# ArduinoStandaloneUsbSwitch-V2.net
KiCad netlist of a schematic drawn in EAGLE
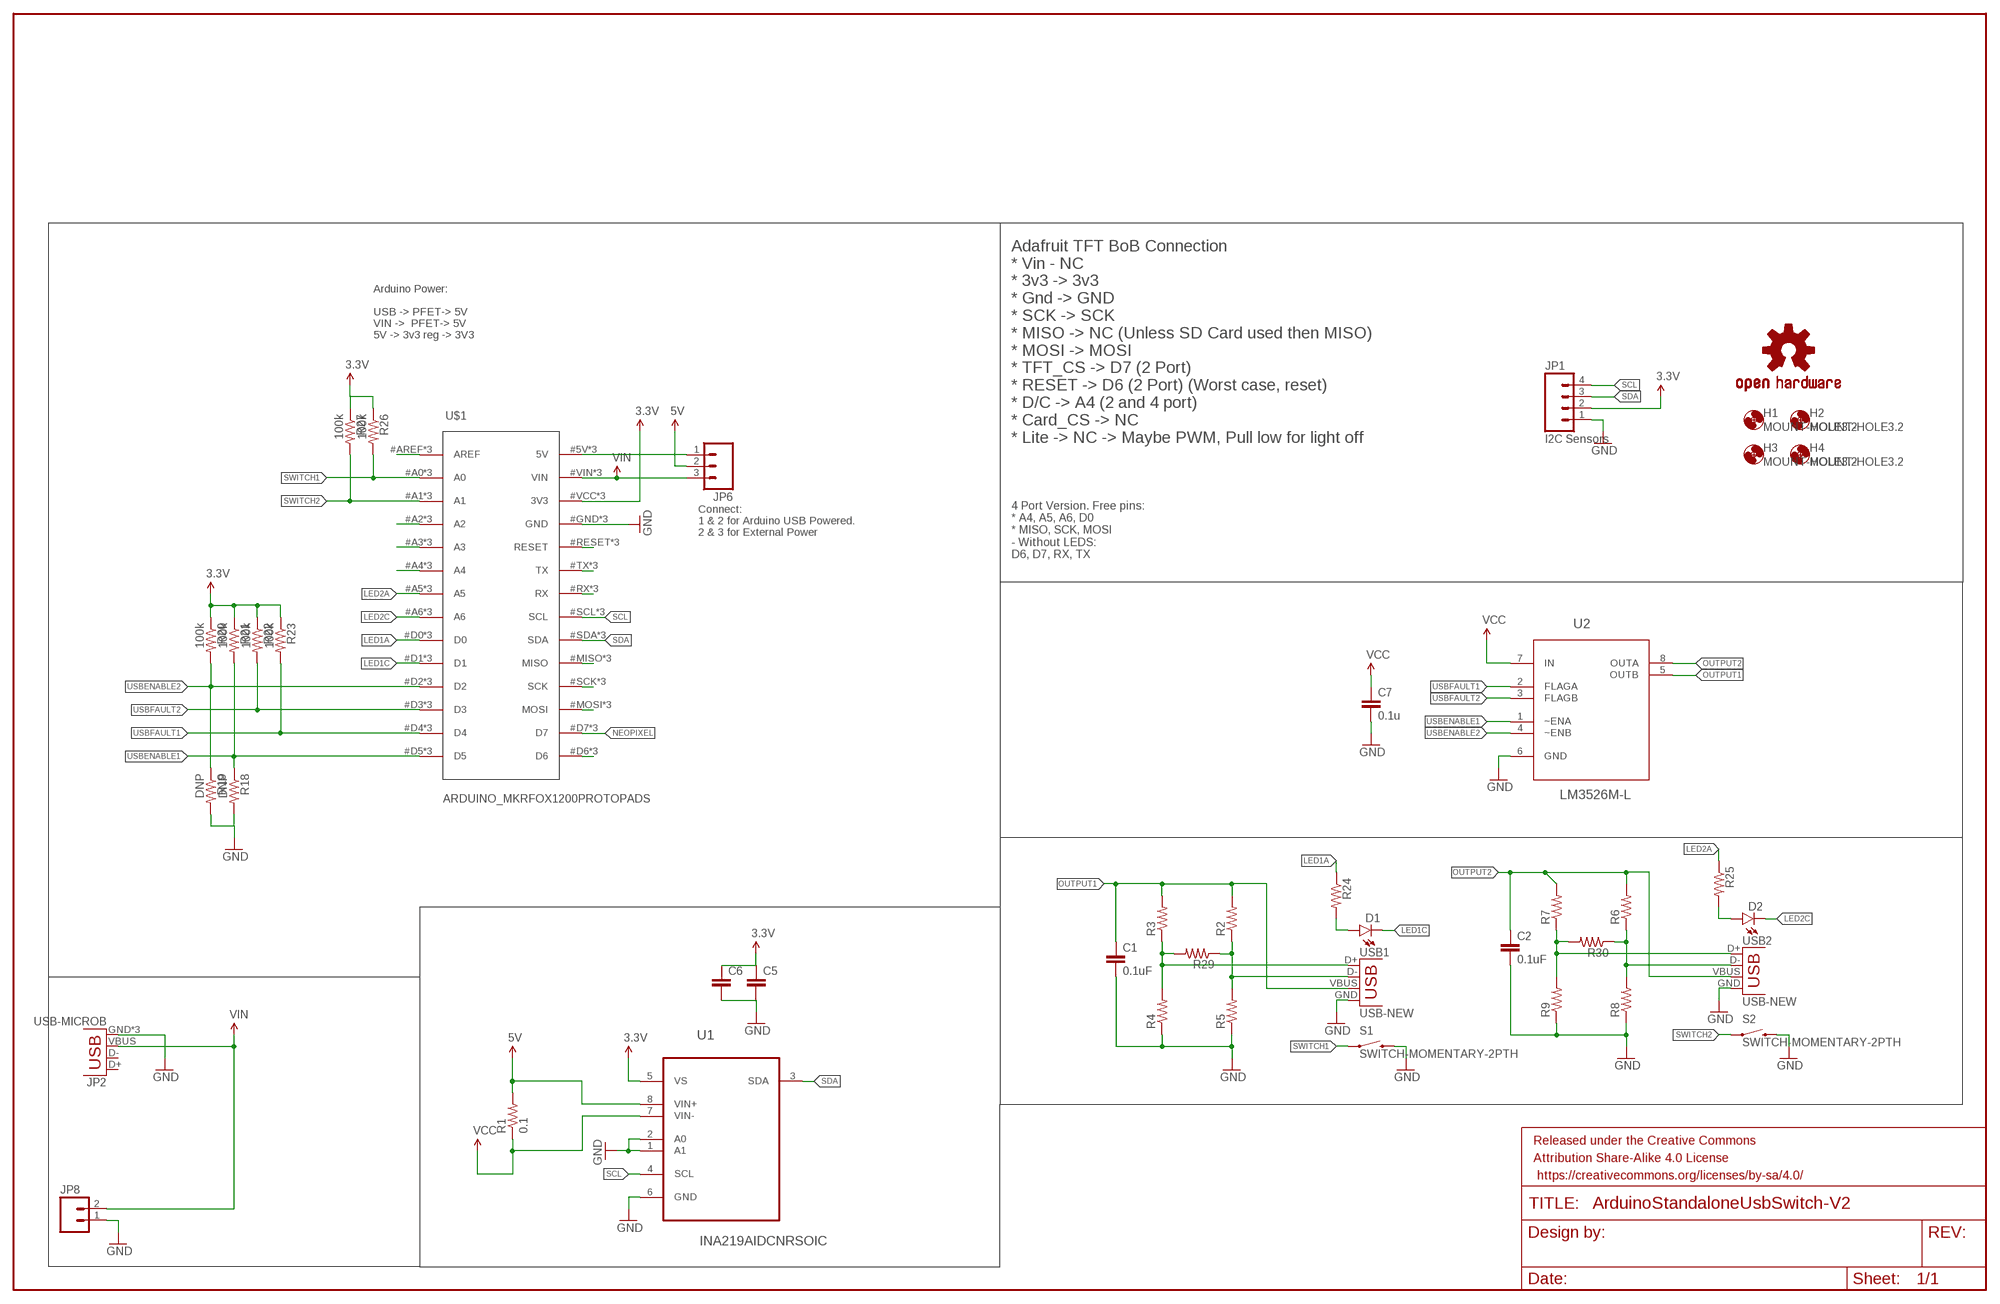
[diagram p0: schematic, sheet 1]

(export (version "E")
  (design (tool "Eeschema 10.0.6"))
  (components
    (comp (ref "C1")
      (value "0.1uF")
      (footprint "eagle-import:0805")
      (libsource (lib "eagle-import") (part "CAP0805"))
    )
    (comp (ref "C2")
      (value "0.1uF")
      (footprint "eagle-import:0805")
      (libsource (lib "eagle-import") (part "CAP0805"))
    )
    (comp (ref "C5")
      (value "CAP0805")
      (footprint "eagle-import:0805")
      (libsource (lib "eagle-import") (part "CAP0805"))
    )
    (comp (ref "C6")
      (value "CAP0805")
      (footprint "eagle-import:0805")
      (libsource (lib "eagle-import") (part "CAP0805"))
    )
    (comp (ref "C7")
      (value "0.1u")
      (footprint "eagle-import:0805")
      (libsource (lib "eagle-import") (part "CAP0805"))
    )
    (comp (ref "D1")
      (value "LED3MM")
      (footprint "eagle-import:LED3MM")
      (libsource (lib "eagle-import") (part "LED3MM"))
    )
    (comp (ref "D2")
      (value "LED3MM")
      (footprint "eagle-import:LED3MM")
      (libsource (lib "eagle-import") (part "LED3MM"))
    )
    (comp (ref "FRAME1")
      (value "FRAME-LEDGER")
      (footprint "eagle-import:CREATIVE_COMMONS")
      (libsource (lib "eagle-import") (part "FRAME-LEDGER"))
    )
    (comp (ref "H1")
      (value "MOUNT-HOLE3.2")
      (footprint "eagle-import:3,2")
      (libsource (lib "eagle-import") (part "MOUNT-HOLE3.2"))
    )
    (comp (ref "H2")
      (value "MOUNT-HOLE3.2")
      (footprint "eagle-import:3,2")
      (libsource (lib "eagle-import") (part "MOUNT-HOLE3.2"))
    )
    (comp (ref "H3")
      (value "MOUNT-HOLE3.2")
      (footprint "eagle-import:3,2")
      (libsource (lib "eagle-import") (part "MOUNT-HOLE3.2"))
    )
    (comp (ref "H4")
      (value "MOUNT-HOLE3.2")
      (footprint "eagle-import:3,2")
      (libsource (lib "eagle-import") (part "MOUNT-HOLE3.2"))
    )
    (comp (ref "JP1")
      (value "I2C Sensors")
      (footprint "eagle-import:MOLEX-1X4")
      (libsource (lib "eagle-import") (part "M04POLAR"))
    )
    (comp (ref "JP2")
      (value "USB-MICROB")
      (footprint "eagle-import:USB-MICROB")
      (libsource (lib "eagle-import") (part "USB-MICROB"))
    )
    (comp (ref "JP6")
      (value "M03PTH")
      (footprint "eagle-import:1X03")
      (libsource (lib "eagle-import") (part "M03PTH"))
    )
    (comp (ref "JP8")
      (value "M025MM")
      (footprint "eagle-import:SCREWTERMINAL-5MM-2")
      (libsource (lib "eagle-import") (part "M025MM"))
    )
    (comp (ref "LOGO1")
      (value "OSHW-LOGOM")
      (footprint "eagle-import:OSHW-LOGO-M")
      (libsource (lib "eagle-import") (part "OSHW-LOGOM"))
    )
    (comp (ref "R1")
      (value "0.1")
      (footprint "eagle-import:2512")
      (libsource (lib "eagle-import") (part "0.001OHM-3W-1%(2512)3W/1%"))
    )
    (comp (ref "R2")
      (value "RESISTOR0805-RES")
      (footprint "eagle-import:0805")
      (libsource (lib "eagle-import") (part "RESISTOR0805-RES"))
    )
    (comp (ref "R3")
      (value "RESISTOR0805-RES")
      (footprint "eagle-import:0805")
      (libsource (lib "eagle-import") (part "RESISTOR0805-RES"))
    )
    (comp (ref "R4")
      (value "RESISTOR0805-RES")
      (footprint "eagle-import:0805")
      (libsource (lib "eagle-import") (part "RESISTOR0805-RES"))
    )
    (comp (ref "R5")
      (value "RESISTOR0805-RES")
      (footprint "eagle-import:0805")
      (libsource (lib "eagle-import") (part "RESISTOR0805-RES"))
    )
    (comp (ref "R6")
      (value "RESISTOR0805-RES")
      (footprint "eagle-import:0805")
      (libsource (lib "eagle-import") (part "RESISTOR0805-RES"))
    )
    (comp (ref "R7")
      (value "RESISTOR0805-RES")
      (footprint "eagle-import:0805")
      (libsource (lib "eagle-import") (part "RESISTOR0805-RES"))
    )
    (comp (ref "R8")
      (value "RESISTOR0805-RES")
      (footprint "eagle-import:0805")
      (libsource (lib "eagle-import") (part "RESISTOR0805-RES"))
    )
    (comp (ref "R9")
      (value "RESISTOR0805-RES")
      (footprint "eagle-import:0805")
      (libsource (lib "eagle-import") (part "RESISTOR0805-RES"))
    )
    (comp (ref "R18")
      (value "DNP")
      (footprint "eagle-import:0805")
      (libsource (lib "eagle-import") (part "RESISTOR0805-RES"))
    )
    (comp (ref "R19")
      (value "DNP")
      (footprint "eagle-import:0805")
      (libsource (lib "eagle-import") (part "RESISTOR0805-RES"))
    )
    (comp (ref "R20")
      (value "100k")
      (footprint "eagle-import:0805")
      (libsource (lib "eagle-import") (part "RESISTOR0805-RES"))
    )
    (comp (ref "R21")
      (value "100k")
      (footprint "eagle-import:0805")
      (libsource (lib "eagle-import") (part "RESISTOR0805-RES"))
    )
    (comp (ref "R22")
      (value "100k")
      (footprint "eagle-import:0805")
      (libsource (lib "eagle-import") (part "RESISTOR0805-RES"))
    )
    (comp (ref "R23")
      (value "100k")
      (footprint "eagle-import:0805")
      (libsource (lib "eagle-import") (part "RESISTOR0805-RES"))
    )
    (comp (ref "R24")
      (value "RESISTOR0805-RES")
      (footprint "eagle-import:0805")
      (libsource (lib "eagle-import") (part "RESISTOR0805-RES"))
    )
    (comp (ref "R25")
      (value "RESISTOR0805-RES")
      (footprint "eagle-import:0805")
      (libsource (lib "eagle-import") (part "RESISTOR0805-RES"))
    )
    (comp (ref "R26")
      (value "100k")
      (footprint "eagle-import:0805")
      (libsource (lib "eagle-import") (part "RESISTOR0805-RES"))
    )
    (comp (ref "R27")
      (value "100k")
      (footprint "eagle-import:0805")
      (libsource (lib "eagle-import") (part "RESISTOR0805-RES"))
    )
    (comp (ref "R29")
      (value "RESISTOR0805-RES")
      (footprint "eagle-import:0805")
      (libsource (lib "eagle-import") (part "RESISTOR0805-RES"))
    )
    (comp (ref "R30")
      (value "RESISTOR0805-RES")
      (footprint "eagle-import:0805")
      (libsource (lib "eagle-import") (part "RESISTOR0805-RES"))
    )
    (comp (ref "S1")
      (value "SWITCH-MOMENTARY-2PTH")
      (footprint "eagle-import:TACTILE-PTH")
      (libsource (lib "eagle-import") (part "SWITCH-MOMENTARY-2PTH"))
    )
    (comp (ref "S2")
      (value "SWITCH-MOMENTARY-2PTH")
      (footprint "eagle-import:TACTILE-PTH")
      (libsource (lib "eagle-import") (part "SWITCH-MOMENTARY-2PTH"))
    )
    (comp (ref "U$1")
      (value "ARDUINO_MKRFOX1200PROTOPADS")
      (footprint "eagle-import:ARDUINO_MKRFOX1200_PROTOPADS")
      (libsource (lib "eagle-import") (part "ARDUINO_MKRFOX1200PROTOPADS"))
    )
    (comp (ref "U1")
      (value "INA219AIDCNRSOIC")
      (footprint "eagle-import:SO08")
      (libsource (lib "eagle-import") (part "INA219AIDCNRSOIC"))
    )
    (comp (ref "U2")
      (value "LM3526M-L")
      (footprint "eagle-import:SOIC127P640X175-8N")
      (libsource (lib "eagle-import") (part "LM3526M-L"))
    )
    (comp (ref "USB1")
      (value "USB-NEW")
      (footprint "eagle-import:USB-A-VERTICAL")
      (libsource (lib "eagle-import") (part "USB-NEW"))
    )
    (comp (ref "USB2")
      (value "USB-NEW")
      (footprint "eagle-import:USB-A-VERTICAL")
      (libsource (lib "eagle-import") (part "USB-NEW"))
    )
  )
  (nets
    (net (code "1") (name "3.3V") (class "Default")
      (node (ref "C5") (pin "1") (pinfunction "1_1") (pintype "passive"))
      (node (ref "C6") (pin "1") (pinfunction "1_1") (pintype "passive"))
      (node (ref "JP1") (pin "2") (pinfunction "2_2") (pintype "passive"))
      (node (ref "R20") (pin "1") (pinfunction "1_1") (pintype "passive"))
      (node (ref "R21") (pin "1") (pinfunction "1_1") (pintype "passive"))
      (node (ref "R22") (pin "1") (pinfunction "1_1") (pintype "passive"))
      (node (ref "R23") (pin "1") (pinfunction "1_1") (pintype "passive"))
      (node (ref "R26") (pin "1") (pinfunction "1_1") (pintype "passive"))
      (node (ref "R27") (pin "1") (pinfunction "1_1") (pintype "passive"))
      (node (ref "U$1") (pin "#VCC") (pinfunction "3V3_#VCC") (pintype "output"))
      (node (ref "U$1") (pin "@VCC") (pinfunction "3V3_@VCC") (pintype "output"))
      (node (ref "U$1") (pin "VCC") (pinfunction "3V3_VCC") (pintype "output"))
      (node (ref "U1") (pin "5") (pinfunction "VS_5") (pintype "power_in"))
    )
    (net (code "2") (name "5V") (class "Default")
      (node (ref "JP6") (pin "2") (pinfunction "2_2") (pintype "passive"))
      (node (ref "R1") (pin "2") (pinfunction "2_2") (pintype "passive"))
      (node (ref "U1") (pin "8") (pinfunction "VIN+_8") (pintype "input"))
    )
    (net (code "3") (name "GND") (class "Default")
      (node (ref "C1") (pin "2") (pinfunction "2_2") (pintype "passive"))
      (node (ref "C2") (pin "2") (pinfunction "2_2") (pintype "passive"))
      (node (ref "C5") (pin "2") (pinfunction "2_2") (pintype "passive"))
      (node (ref "C6") (pin "2") (pinfunction "2_2") (pintype "passive"))
      (node (ref "C7") (pin "2") (pinfunction "2_2") (pintype "passive"))
      (node (ref "JP1") (pin "1") (pinfunction "1_1") (pintype "passive"))
      (node (ref "JP2") (pin "GND") (pinfunction "GND_GND") (pintype "bidirectional"))
      (node (ref "JP2") (pin "MT1") (pinfunction "GND_MT1") (pintype "bidirectional"))
      (node (ref "JP2") (pin "MT2") (pinfunction "GND_MT2") (pintype "bidirectional"))
      (node (ref "JP8") (pin "1") (pinfunction "1_1") (pintype "passive"))
      (node (ref "R18") (pin "2") (pinfunction "2_2") (pintype "passive"))
      (node (ref "R19") (pin "2") (pinfunction "2_2") (pintype "passive"))
      (node (ref "R4") (pin "1") (pinfunction "1_1") (pintype "passive"))
      (node (ref "R5") (pin "1") (pinfunction "1_1") (pintype "passive"))
      (node (ref "R8") (pin "1") (pinfunction "1_1") (pintype "passive"))
      (node (ref "R9") (pin "1") (pinfunction "1_1") (pintype "passive"))
      (node (ref "S1") (pin "3") (pinfunction "2_3") (pintype "passive"))
      (node (ref "S2") (pin "3") (pinfunction "2_3") (pintype "passive"))
      (node (ref "U$1") (pin "#GND") (pinfunction "GND_#GND") (pintype "power_in"))
      (node (ref "U$1") (pin "@GND") (pinfunction "GND_@GND") (pintype "power_in"))
      (node (ref "U$1") (pin "GND") (pinfunction "GND_GND") (pintype "power_in"))
      (node (ref "U1") (pin "1") (pinfunction "A1_1") (pintype "input"))
      (node (ref "U1") (pin "2") (pinfunction "A0_2") (pintype "input"))
      (node (ref "U1") (pin "6") (pinfunction "GND_6") (pintype "passive"))
      (node (ref "U2") (pin "6") (pinfunction "GND_6") (pintype "passive"))
      (node (ref "USB1") (pin "GND") (pinfunction "GND_GND") (pintype "bidirectional"))
      (node (ref "USB2") (pin "GND") (pinfunction "GND_GND") (pintype "bidirectional"))
    )
    (net (code "4") (name "LED1A") (class "Default")
      (node (ref "R24") (pin "1") (pinfunction "1_1") (pintype "passive"))
      (node (ref "U$1") (pin "#D0") (pinfunction "D0_#D0") (pintype "bidirectional"))
      (node (ref "U$1") (pin "@D0") (pinfunction "D0_@D0") (pintype "bidirectional"))
      (node (ref "U$1") (pin "D0") (pinfunction "D0_D0") (pintype "bidirectional"))
    )
    (net (code "5") (name "LED1C") (class "Default")
      (node (ref "D1") (pin "K") (pinfunction "C_K") (pintype "passive"))
      (node (ref "U$1") (pin "#D1") (pinfunction "D1_#D1") (pintype "bidirectional"))
      (node (ref "U$1") (pin "@D1") (pinfunction "D1_@D1") (pintype "bidirectional"))
      (node (ref "U$1") (pin "D1") (pinfunction "D1_D1") (pintype "bidirectional"))
    )
    (net (code "6") (name "LED2A") (class "Default")
      (node (ref "R25") (pin "1") (pinfunction "1_1") (pintype "passive"))
      (node (ref "U$1") (pin "#A5") (pinfunction "A5_#A5") (pintype "bidirectional"))
      (node (ref "U$1") (pin "@A5") (pinfunction "A5_@A5") (pintype "bidirectional"))
      (node (ref "U$1") (pin "A5") (pinfunction "A5_A5") (pintype "bidirectional"))
    )
    (net (code "7") (name "LED2C") (class "Default")
      (node (ref "D2") (pin "K") (pinfunction "C_K") (pintype "passive"))
      (node (ref "U$1") (pin "#A6") (pinfunction "A6_#A6") (pintype "bidirectional"))
      (node (ref "U$1") (pin "@A6") (pinfunction "A6_@A6") (pintype "bidirectional"))
      (node (ref "U$1") (pin "A6") (pinfunction "A6_A6") (pintype "bidirectional"))
    )
    (net (code "8") (name "NEOPIXEL") (class "Default")
      (node (ref "U$1") (pin "#D7") (pinfunction "D7_#D7") (pintype "bidirectional"))
      (node (ref "U$1") (pin "@D7") (pinfunction "D7_@D7") (pintype "bidirectional"))
      (node (ref "U$1") (pin "D7") (pinfunction "D7_D7") (pintype "bidirectional"))
    )
    (net (code "9") (name "Net-(D1-PadA)") (class "Default")
      (node (ref "D1") (pin "A") (pinfunction "A_A") (pintype "passive"))
      (node (ref "R24") (pin "2") (pinfunction "2_2") (pintype "passive"))
    )
    (net (code "10") (name "Net-(D2-PadA)") (class "Default")
      (node (ref "D2") (pin "A") (pinfunction "A_A") (pintype "passive"))
      (node (ref "R25") (pin "2") (pinfunction "2_2") (pintype "passive"))
    )
    (net (code "11") (name "Net-(JP6-Pad1)") (class "Default")
      (node (ref "JP6") (pin "1") (pinfunction "1_1") (pintype "passive"))
      (node (ref "U$1") (pin "#5V") (pinfunction "5V_#5V") (pintype "output"))
      (node (ref "U$1") (pin "5V") (pinfunction "5V_5V") (pintype "output"))
      (node (ref "U$1") (pin "@5V") (pinfunction "5V_@5V") (pintype "output"))
    )
    (net (code "12") (name "Net-(R2-Pad1)") (class "Default")
      (node (ref "R2") (pin "1") (pinfunction "1_1") (pintype "passive"))
      (node (ref "R29") (pin "1") (pinfunction "1_1") (pintype "passive"))
      (node (ref "R5") (pin "2") (pinfunction "2_2") (pintype "passive"))
      (node (ref "USB1") (pin "D-") (pinfunction "D-_D-") (pintype "bidirectional"))
    )
    (net (code "13") (name "Net-(R29-Pad2)") (class "Default")
      (node (ref "R29") (pin "2") (pinfunction "2_2") (pintype "passive"))
      (node (ref "R3") (pin "1") (pinfunction "1_1") (pintype "passive"))
      (node (ref "R4") (pin "2") (pinfunction "2_2") (pintype "passive"))
      (node (ref "USB1") (pin "D+") (pinfunction "D+_D+") (pintype "bidirectional"))
    )
    (net (code "14") (name "Net-(R30-Pad1)") (class "Default")
      (node (ref "R30") (pin "1") (pinfunction "1_1") (pintype "passive"))
      (node (ref "R6") (pin "1") (pinfunction "1_1") (pintype "passive"))
      (node (ref "R8") (pin "2") (pinfunction "2_2") (pintype "passive"))
      (node (ref "USB2") (pin "D-") (pinfunction "D-_D-") (pintype "bidirectional"))
    )
    (net (code "15") (name "Net-(R30-Pad2)") (class "Default")
      (node (ref "R30") (pin "2") (pinfunction "2_2") (pintype "passive"))
      (node (ref "R7") (pin "1") (pinfunction "1_1") (pintype "passive"))
      (node (ref "R9") (pin "2") (pinfunction "2_2") (pintype "passive"))
      (node (ref "USB2") (pin "D+") (pinfunction "D+_D+") (pintype "bidirectional"))
    )
    (net (code "16") (name "Net-(U$1-A2-Pad#A2)") (class "Default")
      (node (ref "U$1") (pin "#A2") (pinfunction "A2_#A2") (pintype "bidirectional"))
      (node (ref "U$1") (pin "@A2") (pinfunction "A2_@A2") (pintype "bidirectional"))
      (node (ref "U$1") (pin "A2") (pinfunction "A2_A2") (pintype "bidirectional"))
    )
    (net (code "17") (name "Net-(U$1-A3-Pad#A3)") (class "Default")
      (node (ref "U$1") (pin "#A3") (pinfunction "A3_#A3") (pintype "bidirectional"))
      (node (ref "U$1") (pin "@A3") (pinfunction "A3_@A3") (pintype "bidirectional"))
      (node (ref "U$1") (pin "A3") (pinfunction "A3_A3") (pintype "bidirectional"))
    )
    (net (code "18") (name "Net-(U$1-A4-Pad#A4)") (class "Default")
      (node (ref "U$1") (pin "#A4") (pinfunction "A4_#A4") (pintype "bidirectional"))
      (node (ref "U$1") (pin "@A4") (pinfunction "A4_@A4") (pintype "bidirectional"))
      (node (ref "U$1") (pin "A4") (pinfunction "A4_A4") (pintype "bidirectional"))
    )
    (net (code "19") (name "Net-(U$1-AREF-Pad#AREF)") (class "Default")
      (node (ref "U$1") (pin "#AREF") (pinfunction "AREF_#AREF") (pintype "bidirectional"))
      (node (ref "U$1") (pin "@AREF") (pinfunction "AREF_@AREF") (pintype "bidirectional"))
      (node (ref "U$1") (pin "AREF") (pinfunction "AREF_AREF") (pintype "bidirectional"))
    )
    (net (code "20") (name "Net-(U$1-D6-Pad#D6)") (class "Default")
      (node (ref "U$1") (pin "#D6") (pinfunction "D6_#D6") (pintype "bidirectional"))
      (node (ref "U$1") (pin "@D6") (pinfunction "D6_@D6") (pintype "bidirectional"))
      (node (ref "U$1") (pin "D6") (pinfunction "D6_D6") (pintype "bidirectional"))
    )
    (net (code "21") (name "Net-(U$1-MISO-Pad#MISO)") (class "Default")
      (node (ref "U$1") (pin "#MISO") (pinfunction "MISO_#MISO") (pintype "bidirectional"))
      (node (ref "U$1") (pin "@MISO") (pinfunction "MISO_@MISO") (pintype "bidirectional"))
      (node (ref "U$1") (pin "MISO") (pinfunction "MISO_MISO") (pintype "bidirectional"))
    )
    (net (code "22") (name "Net-(U$1-MOSI-Pad#MOSI)") (class "Default")
      (node (ref "U$1") (pin "#MOSI") (pinfunction "MOSI_#MOSI") (pintype "bidirectional"))
      (node (ref "U$1") (pin "@MOSI") (pinfunction "MOSI_@MOSI") (pintype "bidirectional"))
      (node (ref "U$1") (pin "MOSI") (pinfunction "MOSI_MOSI") (pintype "bidirectional"))
    )
    (net (code "23") (name "Net-(U$1-PadRESET)") (class "Default")
      (node (ref "U$1") (pin "#RESET") (pinfunction "RESET_#RESET") (pintype "bidirectional"))
      (node (ref "U$1") (pin "@RESET") (pinfunction "RESET_@RESET") (pintype "bidirectional"))
      (node (ref "U$1") (pin "RESET") (pinfunction "RESET_RESET") (pintype "bidirectional"))
    )
    (net (code "24") (name "Net-(U$1-PadRX)") (class "Default")
      (node (ref "U$1") (pin "#RX") (pinfunction "RX_#RX") (pintype "bidirectional"))
      (node (ref "U$1") (pin "@RX") (pinfunction "RX_@RX") (pintype "bidirectional"))
      (node (ref "U$1") (pin "RX") (pinfunction "RX_RX") (pintype "bidirectional"))
    )
    (net (code "25") (name "Net-(U$1-PadSCK)") (class "Default")
      (node (ref "U$1") (pin "#SCK") (pinfunction "SCK_#SCK") (pintype "bidirectional"))
      (node (ref "U$1") (pin "@SCK") (pinfunction "SCK_@SCK") (pintype "bidirectional"))
      (node (ref "U$1") (pin "SCK") (pinfunction "SCK_SCK") (pintype "bidirectional"))
    )
    (net (code "26") (name "Net-(U$1-PadTX)") (class "Default")
      (node (ref "U$1") (pin "#TX") (pinfunction "TX_#TX") (pintype "bidirectional"))
      (node (ref "U$1") (pin "@TX") (pinfunction "TX_@TX") (pintype "bidirectional"))
      (node (ref "U$1") (pin "TX") (pinfunction "TX_TX") (pintype "bidirectional"))
    )
    (net (code "27") (name "OUTPUT1") (class "Default")
      (node (ref "C1") (pin "1") (pinfunction "1_1") (pintype "passive"))
      (node (ref "R2") (pin "2") (pinfunction "2_2") (pintype "passive"))
      (node (ref "R3") (pin "2") (pinfunction "2_2") (pintype "passive"))
      (node (ref "U2") (pin "5") (pinfunction "OUTB_5") (pintype "output"))
      (node (ref "USB1") (pin "VBUS") (pinfunction "VBUS_VBUS") (pintype "bidirectional"))
    )
    (net (code "28") (name "OUTPUT2") (class "Default")
      (node (ref "C2") (pin "1") (pinfunction "1_1") (pintype "passive"))
      (node (ref "R6") (pin "2") (pinfunction "2_2") (pintype "passive"))
      (node (ref "R7") (pin "2") (pinfunction "2_2") (pintype "passive"))
      (node (ref "U2") (pin "8") (pinfunction "OUTA_8") (pintype "output"))
      (node (ref "USB2") (pin "VBUS") (pinfunction "VBUS_VBUS") (pintype "bidirectional"))
    )
    (net (code "29") (name "SCL") (class "Default")
      (node (ref "JP1") (pin "4") (pinfunction "4_4") (pintype "passive"))
      (node (ref "U$1") (pin "#SCL") (pinfunction "SCL_#SCL") (pintype "bidirectional"))
      (node (ref "U$1") (pin "@SCL") (pinfunction "SCL_@SCL") (pintype "bidirectional"))
      (node (ref "U$1") (pin "SCL") (pinfunction "SCL_SCL") (pintype "bidirectional"))
      (node (ref "U1") (pin "4") (pinfunction "SCL_4") (pintype "input"))
    )
    (net (code "30") (name "SDA") (class "Default")
      (node (ref "JP1") (pin "3") (pinfunction "3_3") (pintype "passive"))
      (node (ref "U$1") (pin "#SDA") (pinfunction "SDA_#SDA") (pintype "bidirectional"))
      (node (ref "U$1") (pin "@SDA") (pinfunction "SDA_@SDA") (pintype "bidirectional"))
      (node (ref "U$1") (pin "SDA") (pinfunction "SDA_SDA") (pintype "bidirectional"))
      (node (ref "U1") (pin "3") (pinfunction "SDA_3") (pintype "bidirectional"))
    )
    (net (code "31") (name "SWITCH1") (class "Default")
      (node (ref "R26") (pin "2") (pinfunction "2_2") (pintype "passive"))
      (node (ref "S1") (pin "1") (pinfunction "1_1") (pintype "passive"))
      (node (ref "U$1") (pin "#A0") (pinfunction "A0_#A0") (pintype "bidirectional"))
      (node (ref "U$1") (pin "@A0") (pinfunction "A0_@A0") (pintype "bidirectional"))
      (node (ref "U$1") (pin "A0") (pinfunction "A0_A0") (pintype "bidirectional"))
    )
    (net (code "32") (name "SWITCH2") (class "Default")
      (node (ref "R27") (pin "2") (pinfunction "2_2") (pintype "passive"))
      (node (ref "S2") (pin "1") (pinfunction "1_1") (pintype "passive"))
      (node (ref "U$1") (pin "#A1") (pinfunction "A1_#A1") (pintype "bidirectional"))
      (node (ref "U$1") (pin "@A1") (pinfunction "A1_@A1") (pintype "bidirectional"))
      (node (ref "U$1") (pin "A1") (pinfunction "A1_A1") (pintype "bidirectional"))
    )
    (net (code "33") (name "USBENABLE1") (class "Default")
      (node (ref "R18") (pin "1") (pinfunction "1_1") (pintype "passive"))
      (node (ref "R21") (pin "2") (pinfunction "2_2") (pintype "passive"))
      (node (ref "U$1") (pin "#D5") (pinfunction "D5_#D5") (pintype "bidirectional"))
      (node (ref "U$1") (pin "@D5") (pinfunction "D5_@D5") (pintype "bidirectional"))
      (node (ref "U$1") (pin "D5") (pinfunction "D5_D5") (pintype "bidirectional"))
      (node (ref "U2") (pin "1") (pinfunction "~{ENA}_1") (pintype "input"))
    )
    (net (code "34") (name "USBENABLE2") (class "Default")
      (node (ref "R19") (pin "1") (pinfunction "1_1") (pintype "passive"))
      (node (ref "R20") (pin "2") (pinfunction "2_2") (pintype "passive"))
      (node (ref "U$1") (pin "#D2") (pinfunction "D2_#D2") (pintype "bidirectional"))
      (node (ref "U$1") (pin "@D2") (pinfunction "D2_@D2") (pintype "bidirectional"))
      (node (ref "U$1") (pin "D2") (pinfunction "D2_D2") (pintype "bidirectional"))
      (node (ref "U2") (pin "4") (pinfunction "~{ENB}_4") (pintype "input"))
    )
    (net (code "35") (name "USBFAULT1") (class "Default")
      (node (ref "R23") (pin "2") (pinfunction "2_2") (pintype "passive"))
      (node (ref "U$1") (pin "#D4") (pinfunction "D4_#D4") (pintype "bidirectional"))
      (node (ref "U$1") (pin "@D4") (pinfunction "D4_@D4") (pintype "bidirectional"))
      (node (ref "U$1") (pin "D4") (pinfunction "D4_D4") (pintype "bidirectional"))
      (node (ref "U2") (pin "2") (pinfunction "FLAGA_2") (pintype "input"))
    )
    (net (code "36") (name "USBFAULT2") (class "Default")
      (node (ref "R22") (pin "2") (pinfunction "2_2") (pintype "passive"))
      (node (ref "U$1") (pin "#D3") (pinfunction "D3_#D3") (pintype "bidirectional"))
      (node (ref "U$1") (pin "@D3") (pinfunction "D3_@D3") (pintype "bidirectional"))
      (node (ref "U$1") (pin "D3") (pinfunction "D3_D3") (pintype "bidirectional"))
      (node (ref "U2") (pin "3") (pinfunction "FLAGB_3") (pintype "input"))
    )
    (net (code "37") (name "VCC") (class "Default")
      (node (ref "C7") (pin "1") (pinfunction "1_1") (pintype "passive"))
      (node (ref "R1") (pin "1") (pinfunction "1_1") (pintype "passive"))
      (node (ref "U1") (pin "7") (pinfunction "VIN-_7") (pintype "input"))
      (node (ref "U2") (pin "7") (pinfunction "IN_7") (pintype "power_in"))
    )
    (net (code "38") (name "VIN") (class "Default")
      (node (ref "JP2") (pin "VBUS") (pinfunction "VBUS_VBUS") (pintype "bidirectional"))
      (node (ref "JP6") (pin "3") (pinfunction "3_3") (pintype "passive"))
      (node (ref "JP8") (pin "2") (pinfunction "2_2") (pintype "passive"))
      (node (ref "U$1") (pin "#VIN") (pinfunction "VIN_#VIN") (pintype "input"))
      (node (ref "U$1") (pin "@VIN") (pinfunction "VIN_@VIN") (pintype "input"))
      (node (ref "U$1") (pin "VIN") (pinfunction "VIN_VIN") (pintype "input"))
    )
    (net (code "39") (name "unconnected-(JP2-PadD+)") (class "Default")
      (node (ref "JP2") (pin "D+") (pinfunction "D+_D+") (pintype "bidirectional"))
    )
    (net (code "40") (name "unconnected-(JP2-PadD-)") (class "Default")
      (node (ref "JP2") (pin "D-") (pinfunction "D-_D-") (pintype "bidirectional"))
    )
  )
)
